# TwistIt.net
KiCad netlist of a schematic drawn in EAGLE
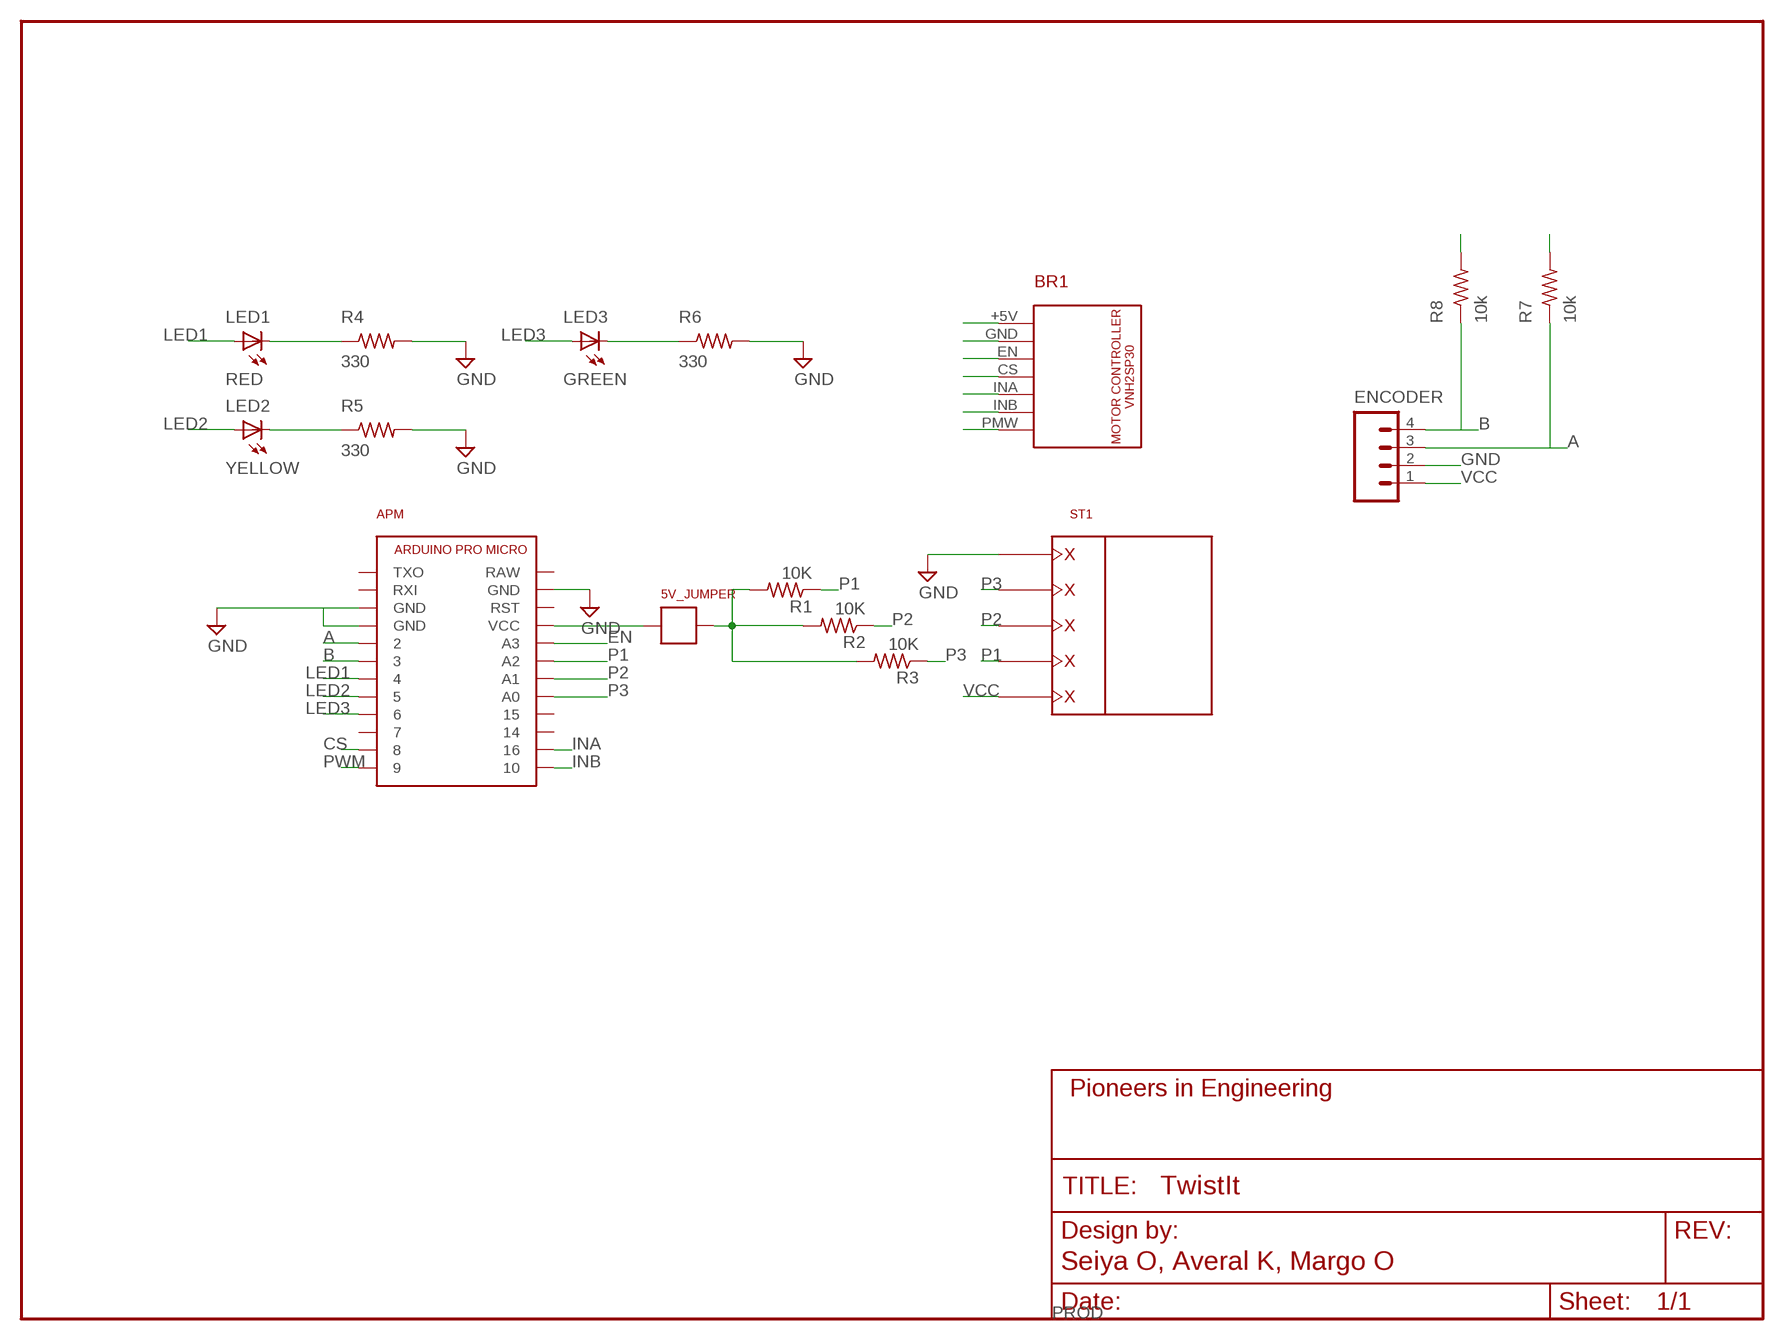
[diagram p0: schematic, sheet 1]

(export (version "E")
  (design (tool "Eeschema 10.0.6"))
  (components
    (comp (ref "5V_JUMPER")
      (value "JUMPER")
      (footprint "eagle-import:JUMPER")
      (fields
        (field (name "DISTRIBUTOR_PART_NUMBER") "952-2262-ND")
        (field (name "MANUFACTURER") "Harwin. Inc")
        (field (name "MANUFACTURER_PART_NUMBER") "M20-9990246")
      )
      (libsource (lib "eagle-import") (part "JUMPER"))
    )
    (comp (ref "APM")
      (value "ARDUINO_PRO_MICRO")
      (footprint "eagle-import:ARDUINO_PRO_MICRO")
      (fields
        (field (name "DISTRIBUTOR_PART_NUMBER") "32284746884")
        (field (name "MANUFACTURER") "Feiyang electronics")
      )
      (libsource (lib "eagle-import") (part "ARDUINO_PRO_MICRO"))
    )
    (comp (ref "BR1")
      (value "VNH2SP30_MOTOR_CONTROLLER")
      (footprint "eagle-import:VNH2SP30_MOTOR_CONTROLLER")
      (libsource (lib "eagle-import") (part "VNH2SP30_MOTOR_CONTROLLER"))
    )
    (comp (ref "ENCODER")
      (value "M041X04-MTA")
      (footprint "eagle-import:1X04-MTA")
      (libsource (lib "eagle-import") (part "M041X04-MTA"))
    )
    (comp (ref "LED1")
      (value "RED")
      (footprint "eagle-import:LED-1206")
      (libsource (lib "eagle-import") (part "LED1206"))
    )
    (comp (ref "LED2")
      (value "YELLOW")
      (footprint "eagle-import:LED-1206")
      (libsource (lib "eagle-import") (part "LED1206"))
    )
    (comp (ref "LED3")
      (value "GREEN")
      (footprint "eagle-import:LED-1206")
      (libsource (lib "eagle-import") (part "LED1206"))
    )
    (comp (ref "R1")
      (value "10K")
      (footprint "eagle-import:R0603")
      (libsource (lib "eagle-import") (part "resistor_348_R-US_R0603"))
    )
    (comp (ref "R2")
      (value "10K")
      (footprint "eagle-import:R0603")
      (libsource (lib "eagle-import") (part "resistor_348_R-US_R0603"))
    )
    (comp (ref "R3")
      (value "10K")
      (footprint "eagle-import:R0603")
      (libsource (lib "eagle-import") (part "resistor_348_R-US_R0603"))
    )
    (comp (ref "R4")
      (value "330")
      (footprint "eagle-import:R0603")
      (fields (field (name "MANUFACTURER") "Rohm Semiconductor"))
      (libsource (lib "eagle-import") (part "R-US_R0603"))
    )
    (comp (ref "R5")
      (value "330")
      (footprint "eagle-import:R0603")
      (fields (field (name "MANUFACTURER") "Rohm Semiconductor"))
      (libsource (lib "eagle-import") (part "R-US_R0603"))
    )
    (comp (ref "R6")
      (value "330")
      (footprint "eagle-import:R0603")
      (fields (field (name "MANUFACTURER") "Rohm Semiconductor"))
      (libsource (lib "eagle-import") (part "R-US_R0603"))
    )
    (comp (ref "R7")
      (value "10k")
      (footprint "eagle-import:R0603")
      (fields (field (name "MANUFACTURER") "Rohm Semiconductor"))
      (libsource (lib "eagle-import") (part "R-US_R0603"))
    )
    (comp (ref "R8")
      (value "10k")
      (footprint "eagle-import:R0603")
      (fields (field (name "MANUFACTURER") "Rohm Semiconductor"))
      (libsource (lib "eagle-import") (part "R-US_R0603"))
    )
    (comp (ref "ST1")
      (value "5PIN_SCREW")
      (footprint "eagle-import:5PIN_SCREW")
      (fields
        (field (name "DISTRIBUTOR_PART_NUMBER") "277-1239-ND")
        (field (name "MANUFACTURER") "Phoenix Contact")
        (field (name "MANUFACTURER_PART_NUMBER") "1729047")
      )
      (libsource (lib "eagle-import") (part "5PIN_SCREW"))
    )
  )
  (nets
    (net (code "1") (name "/A") (class "Default")
      (node (ref "APM") (pin "2") (pinfunction "2_2") (pintype "bidirectional"))
      (node (ref "ENCODER") (pin "3") (pinfunction "3_3") (pintype "passive"))
      (node (ref "R7") (pin "1") (pinfunction "1_1") (pintype "passive"))
    )
    (net (code "2") (name "/B") (class "Default")
      (node (ref "APM") (pin "3") (pinfunction "3_3") (pintype "bidirectional"))
      (node (ref "ENCODER") (pin "4") (pinfunction "4_4") (pintype "passive"))
      (node (ref "R8") (pin "1") (pinfunction "1_1") (pintype "passive"))
    )
    (net (code "3") (name "/CS") (class "Default")
      (node (ref "APM") (pin "8") (pinfunction "8_8") (pintype "bidirectional"))
      (node (ref "BR1") (pin "CS") (pinfunction "CS_CS") (pintype "bidirectional"))
    )
    (net (code "4") (name "/EN") (class "Default")
      (node (ref "APM") (pin "A3") (pinfunction "A3_A3") (pintype "bidirectional"))
      (node (ref "BR1") (pin "EN") (pinfunction "EN_EN") (pintype "bidirectional"))
    )
    (net (code "5") (name "/INA") (class "Default")
      (node (ref "APM") (pin "16") (pinfunction "16_16") (pintype "bidirectional"))
      (node (ref "BR1") (pin "INA") (pinfunction "INA_INA") (pintype "bidirectional"))
    )
    (net (code "6") (name "/INB") (class "Default")
      (node (ref "APM") (pin "10") (pinfunction "10_10") (pintype "bidirectional"))
      (node (ref "BR1") (pin "INB") (pinfunction "INB_INB") (pintype "bidirectional"))
    )
    (net (code "7") (name "/LED1") (class "Default")
      (node (ref "APM") (pin "4") (pinfunction "4_4") (pintype "bidirectional"))
      (node (ref "LED1") (pin "A") (pinfunction "A_A") (pintype "passive"))
    )
    (net (code "8") (name "/LED2") (class "Default")
      (node (ref "APM") (pin "5") (pinfunction "5_5") (pintype "bidirectional"))
      (node (ref "LED2") (pin "A") (pinfunction "A_A") (pintype "passive"))
    )
    (net (code "9") (name "/LED3") (class "Default")
      (node (ref "APM") (pin "6") (pinfunction "6_6") (pintype "bidirectional"))
      (node (ref "LED3") (pin "A") (pinfunction "A_A") (pintype "passive"))
    )
    (net (code "10") (name "/P1") (class "Default")
      (node (ref "APM") (pin "A2") (pinfunction "A2_A2") (pintype "bidirectional"))
      (node (ref "R1") (pin "1") (pinfunction "1_1") (pintype "passive"))
      (node (ref "ST1") (pin "P$4") (pinfunction "P$4_P$4") (pintype "bidirectional"))
    )
    (net (code "11") (name "/P2") (class "Default")
      (node (ref "APM") (pin "A1") (pinfunction "A1_A1") (pintype "bidirectional"))
      (node (ref "R2") (pin "1") (pinfunction "1_1") (pintype "passive"))
      (node (ref "ST1") (pin "P$3") (pinfunction "P$3_P$3") (pintype "bidirectional"))
    )
    (net (code "12") (name "/P3") (class "Default")
      (node (ref "APM") (pin "A0") (pinfunction "A0_A0") (pintype "bidirectional"))
      (node (ref "R3") (pin "1") (pinfunction "1_1") (pintype "passive"))
      (node (ref "ST1") (pin "P$2") (pinfunction "P$2_P$2") (pintype "bidirectional"))
    )
    (net (code "13") (name "/PWM") (class "Default")
      (node (ref "APM") (pin "9") (pinfunction "9_9") (pintype "bidirectional"))
      (node (ref "BR1") (pin "PMW") (pinfunction "PWM_PMW") (pintype "bidirectional"))
    )
    (net (code "14") (name "/VCC") (class "Default")
      (node (ref "5V_JUMPER") (pin "P$1") (pinfunction "P$1_P$1") (pintype "input"))
      (node (ref "APM") (pin "VCC") (pinfunction "VCC_VCC") (pintype "bidirectional"))
      (node (ref "BR1") (pin "+5V") (pinfunction "+5V_+5V") (pintype "bidirectional"))
      (node (ref "ENCODER") (pin "1") (pinfunction "1_1") (pintype "passive"))
      (node (ref "R7") (pin "2") (pinfunction "2_2") (pintype "passive"))
      (node (ref "R8") (pin "2") (pinfunction "2_2") (pintype "passive"))
      (node (ref "ST1") (pin "P$5") (pinfunction "P$5_P$5") (pintype "bidirectional"))
    )
    (net (code "15") (name "GND") (class "Default")
      (node (ref "APM") (pin "GND@0") (pinfunction "GND_GND@0") (pintype "bidirectional"))
      (node (ref "APM") (pin "GND@1") (pinfunction "GND_GND@1") (pintype "bidirectional"))
      (node (ref "APM") (pin "GND@2") (pinfunction "GND_GND@2") (pintype "bidirectional"))
      (node (ref "BR1") (pin "GND") (pinfunction "GND_GND") (pintype "bidirectional"))
      (node (ref "ENCODER") (pin "2") (pinfunction "2_2") (pintype "passive"))
      (node (ref "R4") (pin "2") (pinfunction "2_2") (pintype "passive"))
      (node (ref "R5") (pin "2") (pinfunction "2_2") (pintype "passive"))
      (node (ref "R6") (pin "2") (pinfunction "2_2") (pintype "passive"))
      (node (ref "ST1") (pin "P$1") (pinfunction "P$1_P$1") (pintype "bidirectional"))
    )
    (net (code "16") (name "Net-(5V_JUMPER-PadP$2)") (class "Default")
      (node (ref "5V_JUMPER") (pin "P$2") (pinfunction "P$2_P$2") (pintype "bidirectional"))
      (node (ref "R1") (pin "2") (pinfunction "2_2") (pintype "passive"))
      (node (ref "R2") (pin "2") (pinfunction "2_2") (pintype "passive"))
      (node (ref "R3") (pin "2") (pinfunction "2_2") (pintype "passive"))
    )
    (net (code "17") (name "Net-(LED1-PadC)") (class "Default")
      (node (ref "LED1") (pin "C") (pinfunction "C_C") (pintype "passive"))
      (node (ref "R4") (pin "1") (pinfunction "1_1") (pintype "passive"))
    )
    (net (code "18") (name "Net-(LED2-PadC)") (class "Default")
      (node (ref "LED2") (pin "C") (pinfunction "C_C") (pintype "passive"))
      (node (ref "R5") (pin "1") (pinfunction "1_1") (pintype "passive"))
    )
    (net (code "19") (name "Net-(LED3-PadC)") (class "Default")
      (node (ref "LED3") (pin "C") (pinfunction "C_C") (pintype "passive"))
      (node (ref "R6") (pin "1") (pinfunction "1_1") (pintype "passive"))
    )
    (net (code "20") (name "unconnected-(APM-Pad7)") (class "Default")
      (node (ref "APM") (pin "7") (pinfunction "7_7") (pintype "bidirectional"))
    )
    (net (code "21") (name "unconnected-(APM-Pad14)") (class "Default")
      (node (ref "APM") (pin "14") (pinfunction "14_14") (pintype "bidirectional"))
    )
    (net (code "22") (name "unconnected-(APM-Pad15)") (class "Default")
      (node (ref "APM") (pin "15") (pinfunction "15_15") (pintype "bidirectional"))
    )
    (net (code "23") (name "unconnected-(APM-PadRAW)") (class "Default")
      (node (ref "APM") (pin "RAW") (pinfunction "RAW_RAW") (pintype "bidirectional"))
    )
    (net (code "24") (name "unconnected-(APM-PadRST)") (class "Default")
      (node (ref "APM") (pin "RST") (pinfunction "RST_RST") (pintype "bidirectional"))
    )
    (net (code "25") (name "unconnected-(APM-PadRXI)") (class "Default")
      (node (ref "APM") (pin "RXI") (pinfunction "RXI_RXI") (pintype "bidirectional"))
    )
    (net (code "26") (name "unconnected-(APM-PadTXO)") (class "Default")
      (node (ref "APM") (pin "TXO") (pinfunction "TXO_TXO") (pintype "bidirectional"))
    )
  )
)
